# teste1.net
KiCad netlist of a schematic drawn in EAGLE
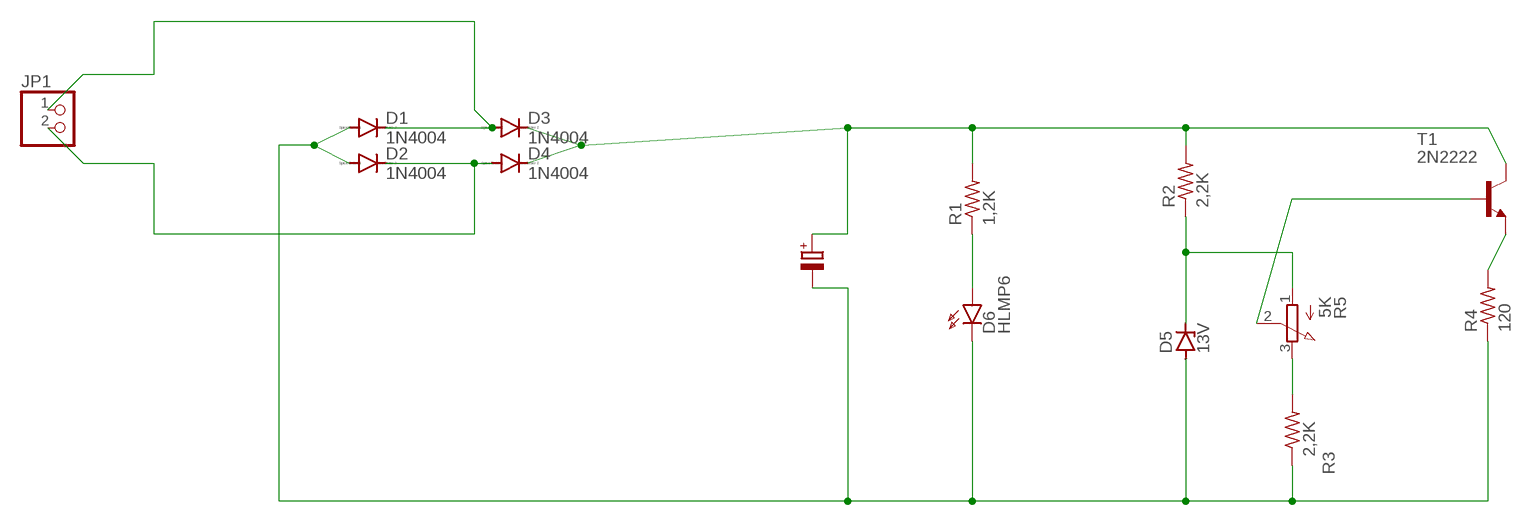
[diagram p0: schematic, sheet 1]

(export (version "E")
  (design (tool "Eeschema 10.0.6"))
  (components
    (comp (ref "D1")
      (value "1N4004")
      (footprint "eagle-import:DO41-10")
      (libsource (lib "eagle-import") (part "1N4004"))
    )
    (comp (ref "D2")
      (value "1N4004")
      (footprint "eagle-import:DO41-10")
      (libsource (lib "eagle-import") (part "1N4004"))
    )
    (comp (ref "D3")
      (value "1N4004")
      (footprint "eagle-import:DO41-10")
      (libsource (lib "eagle-import") (part "1N4004"))
    )
    (comp (ref "D4")
      (value "1N4004")
      (footprint "eagle-import:DO41-10")
      (libsource (lib "eagle-import") (part "1N4004"))
    )
    (comp (ref "D5")
      (value "13V")
      (footprint "eagle-import:SOD81")
      (libsource (lib "eagle-import") (part "BZD23"))
    )
    (comp (ref "D6")
      (value "HLMP6")
      (footprint "eagle-import:HLMP6")
      (fields (field (name "MF") "AGILENT TECHNOLOGIES") (field (name "MPN") "HLMP-6500"))
      (libsource (lib "eagle-import") (part "HLMP6"))
    )
    (comp (ref "JP1")
      (value "PINHD-1X2")
      (footprint "eagle-import:1X02")
      (libsource (lib "eagle-import") (part "PINHD-1X2"))
    )
    (comp (ref "R1")
      (value "1,2K")
      (footprint "eagle-import:P0613_15")
      (libsource (lib "eagle-import") (part "R-US_0613/15"))
    )
    (comp (ref "R2")
      (value "2,2K")
      (footprint "eagle-import:P0613_15")
      (libsource (lib "eagle-import") (part "R-US_0613/15"))
    )
    (comp (ref "R3")
      (value "2,2K")
      (footprint "eagle-import:P0613_15")
      (libsource (lib "eagle-import") (part "R-US_0613/15"))
    )
    (comp (ref "R4")
      (value "120")
      (footprint "eagle-import:P0613_15")
      (libsource (lib "eagle-import") (part "R-US_0613/15"))
    )
    (comp (ref "R5")
      (value "5K")
      (footprint "eagle-import:EVUF")
      (libsource (lib "eagle-import") (part "EVUAF2"))
    )
    (comp (ref "T1")
      (value "2N2222")
      (footprint "eagle-import:TO18")
      (libsource (lib "eagle-import") (part "2N2222"))
    )
  )
  (nets
    (net (code "1") (name "Net-(D1-PadA)") (class "Default")
      (node (ref "D1") (pin "A") (pinfunction "A_A") (pintype "passive"))
      (node (ref "D2") (pin "A") (pinfunction "A_A") (pintype "passive"))
      (node (ref "D5") (pin "A") (pinfunction "A_A") (pintype "passive"))
      (node (ref "D6") (pin "K") (pinfunction "K_K") (pintype "passive"))
      (node (ref "R3") (pin "1") (pinfunction "1_1") (pintype "passive"))
      (node (ref "R4") (pin "1") (pinfunction "1_1") (pintype "passive"))
    )
    (net (code "2") (name "Net-(D1-PadC)") (class "Default")
      (node (ref "D1") (pin "C") (pinfunction "C_C") (pintype "passive"))
      (node (ref "D3") (pin "A") (pinfunction "A_A") (pintype "passive"))
      (node (ref "JP1") (pin "1") (pinfunction "1_1") (pintype "passive"))
    )
    (net (code "3") (name "Net-(D2-PadC)") (class "Default")
      (node (ref "D2") (pin "C") (pinfunction "C_C") (pintype "passive"))
      (node (ref "D4") (pin "A") (pinfunction "A_A") (pintype "passive"))
      (node (ref "JP1") (pin "2") (pinfunction "2_2") (pintype "passive"))
    )
    (net (code "4") (name "Net-(D6-PadA)") (class "Default")
      (node (ref "D6") (pin "A") (pinfunction "A_A") (pintype "passive"))
      (node (ref "R1") (pin "1") (pinfunction "1_1") (pintype "passive"))
    )
    (net (code "5") (name "Net-(R5-A)") (class "Default")
      (node (ref "D5") (pin "C") (pinfunction "C_C") (pintype "passive"))
      (node (ref "R2") (pin "1") (pinfunction "1_1") (pintype "passive"))
      (node (ref "R5") (pin "1") (pinfunction "A_1") (pintype "passive"))
    )
    (net (code "6") (name "Net-(R5-E)") (class "Default")
      (node (ref "R3") (pin "2") (pinfunction "2_2") (pintype "passive"))
      (node (ref "R5") (pin "3") (pinfunction "E_3") (pintype "passive"))
    )
    (net (code "7") (name "Net-(R5-S)") (class "Default")
      (node (ref "R5") (pin "2") (pinfunction "S_2") (pintype "passive"))
      (node (ref "T1") (pin "2") (pinfunction "B_2") (pintype "passive"))
    )
    (net (code "8") (name "Net-(T1-C)") (class "Default")
      (node (ref "D3") (pin "C") (pinfunction "C_C") (pintype "passive"))
      (node (ref "D4") (pin "C") (pinfunction "C_C") (pintype "passive"))
      (node (ref "R1") (pin "2") (pinfunction "2_2") (pintype "passive"))
      (node (ref "R2") (pin "2") (pinfunction "2_2") (pintype "passive"))
      (node (ref "T1") (pin "3") (pinfunction "C_3") (pintype "passive"))
    )
    (net (code "9") (name "Net-(T1-E)") (class "Default")
      (node (ref "R4") (pin "2") (pinfunction "2_2") (pintype "passive"))
      (node (ref "T1") (pin "1") (pinfunction "E_1") (pintype "passive"))
    )
  )
)
